# FinalSch.net
KiCad netlist of a schematic drawn in EAGLE
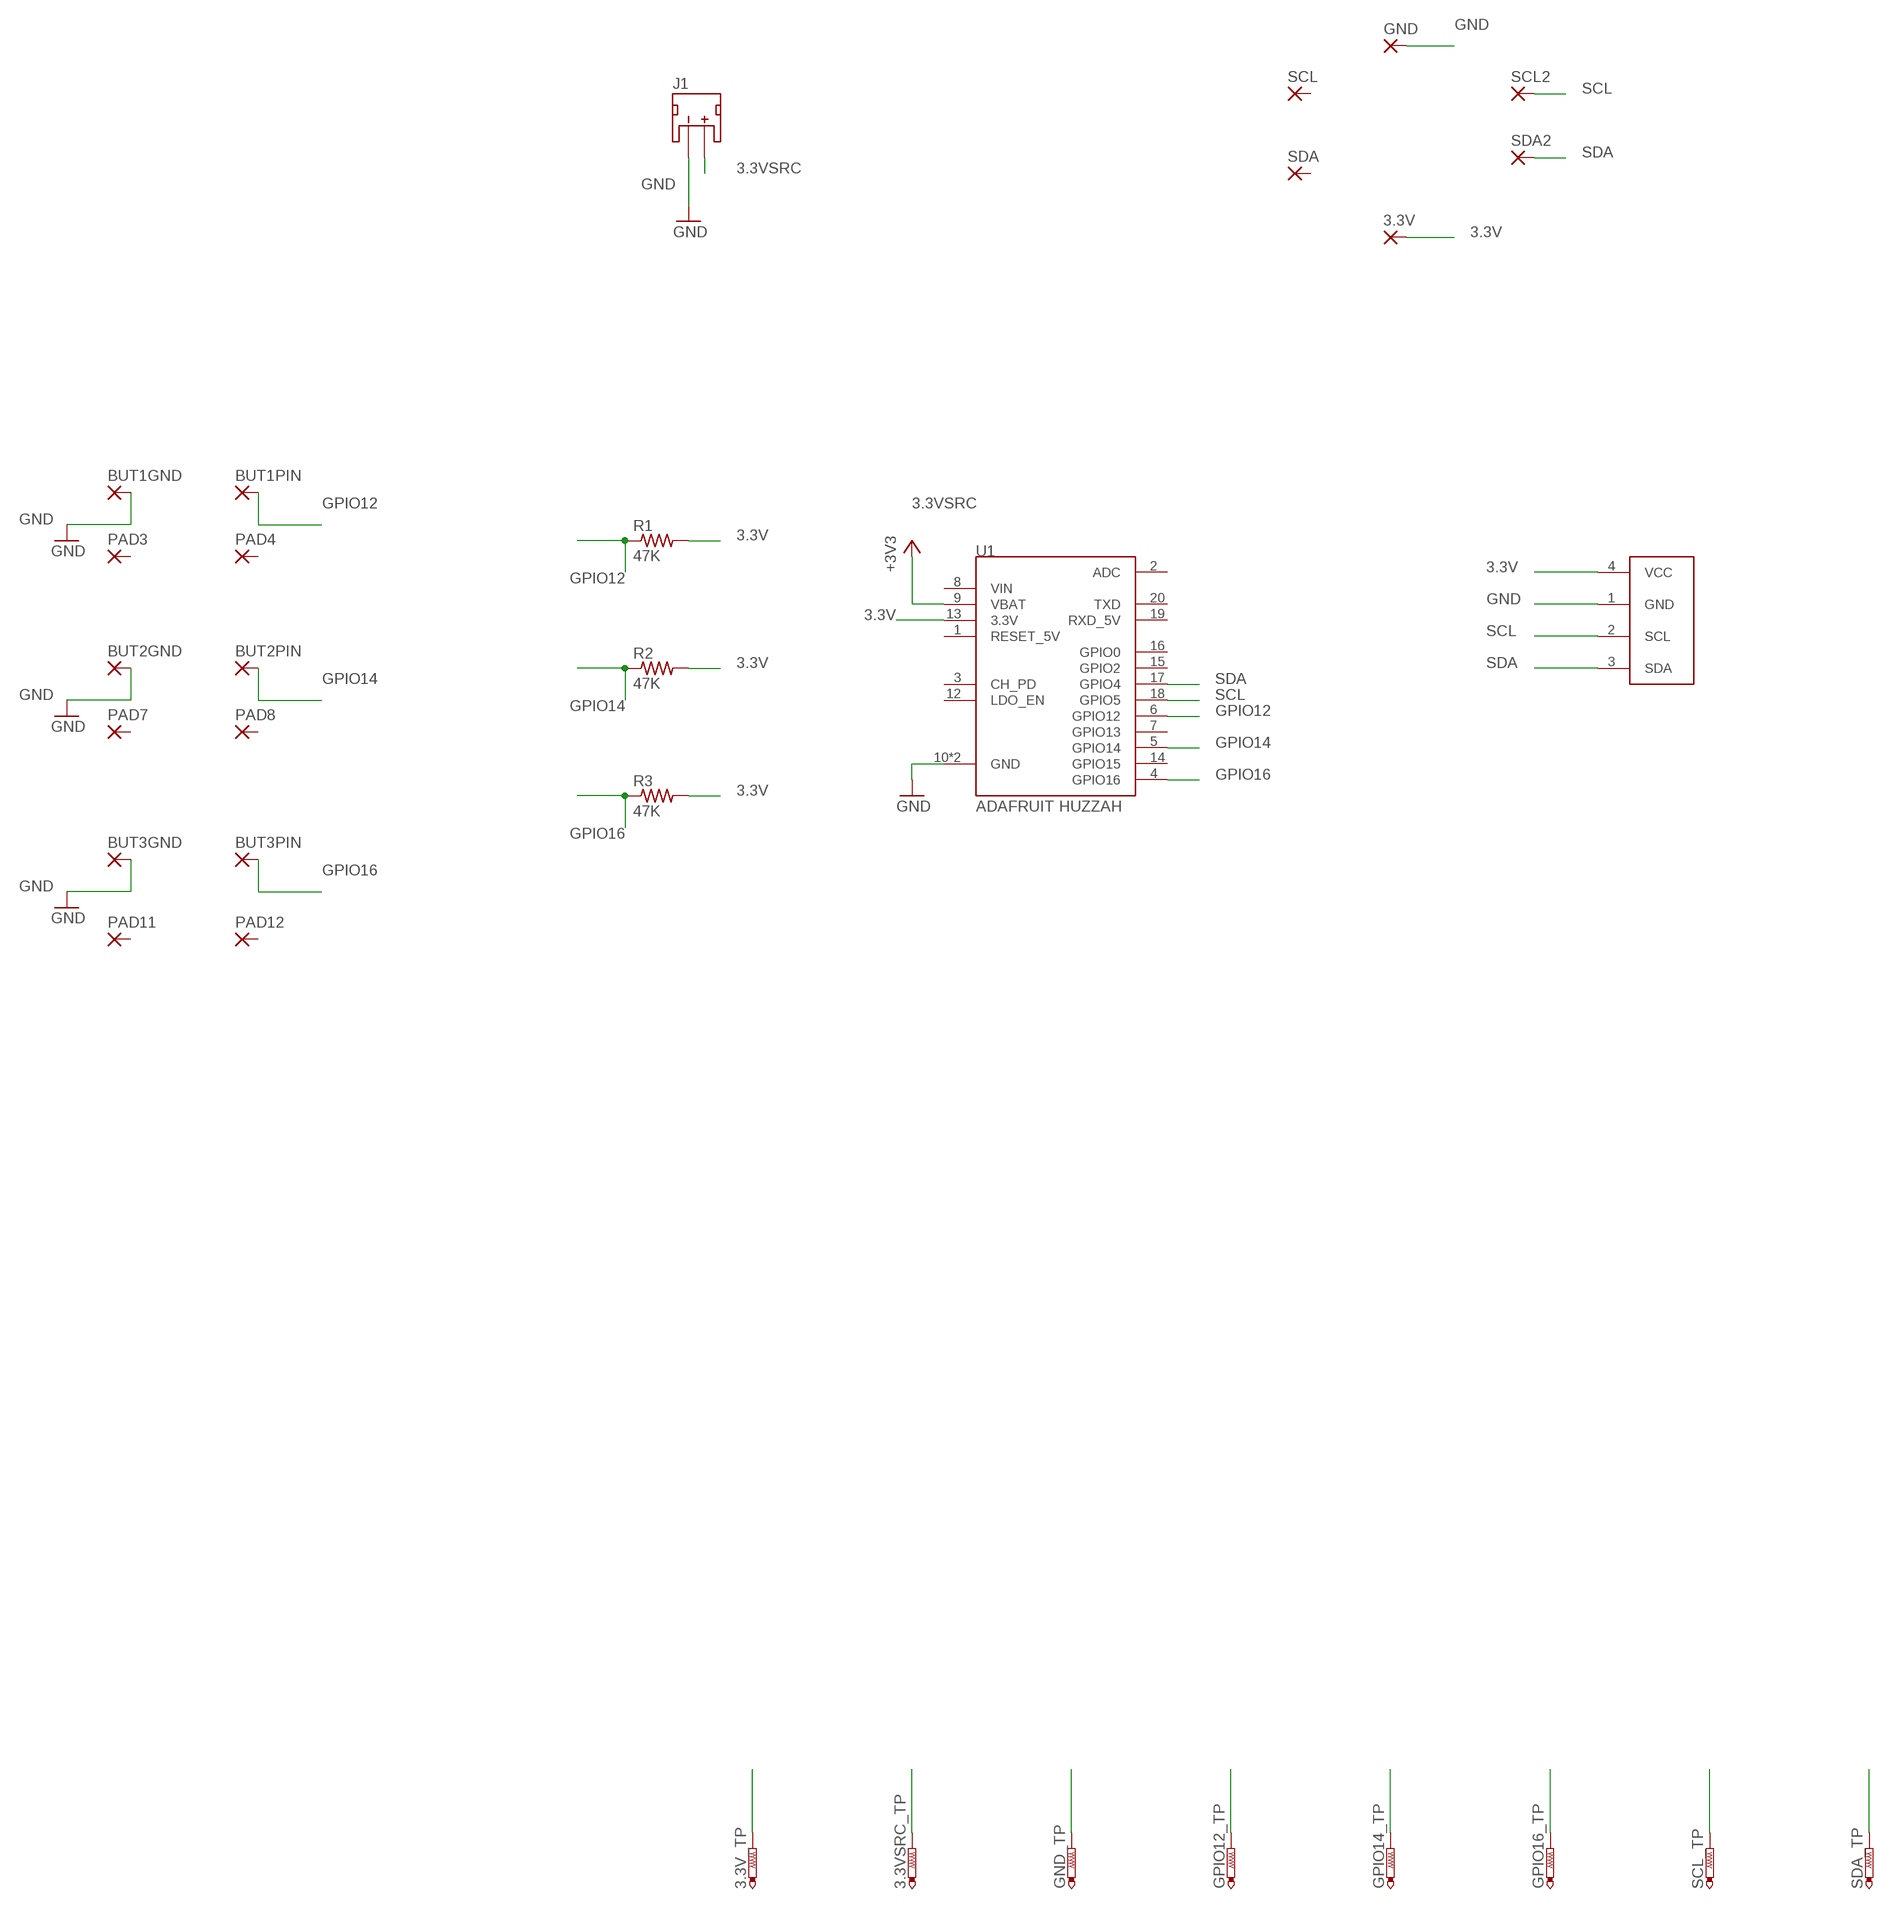
[diagram p0: schematic, sheet 1]

(export (version "E")
  (design (tool "Eeschema 10.0.6"))
  (components
    (comp (ref "3.3V")
      (value "2,54/1,1")
      (footprint "eagle-import:2,54_1,1")
      (libsource (lib "eagle-import") (part "2,54/1,1"))
    )
    (comp (ref "3.3VSRC_TP")
      (value "PTR1B1,27")
      (footprint "eagle-import:B1,27")
      (libsource (lib "eagle-import") (part "PTR1B1,27"))
    )
    (comp (ref "3.3V_TP")
      (value "PTR1B1,27")
      (footprint "eagle-import:B1,27")
      (libsource (lib "eagle-import") (part "PTR1B1,27"))
    )
    (comp (ref "BUT1GND")
      (value "SMD2")
      (footprint "eagle-import:SMD1,27-2,54")
      (libsource (lib "eagle-import") (part "SMD2"))
    )
    (comp (ref "BUT1PIN")
      (value "SMD2")
      (footprint "eagle-import:SMD1,27-2,54")
      (libsource (lib "eagle-import") (part "SMD2"))
    )
    (comp (ref "BUT2GND")
      (value "SMD2")
      (footprint "eagle-import:SMD1,27-2,54")
      (libsource (lib "eagle-import") (part "SMD2"))
    )
    (comp (ref "BUT2PIN")
      (value "SMD2")
      (footprint "eagle-import:SMD1,27-2,54")
      (libsource (lib "eagle-import") (part "SMD2"))
    )
    (comp (ref "BUT3GND")
      (value "SMD2")
      (footprint "eagle-import:SMD1,27-2,54")
      (libsource (lib "eagle-import") (part "SMD2"))
    )
    (comp (ref "BUT3PIN")
      (value "SMD2")
      (footprint "eagle-import:SMD1,27-2,54")
      (libsource (lib "eagle-import") (part "SMD2"))
    )
    (comp (ref "GND")
      (value "2,54/1,1")
      (footprint "eagle-import:2,54_1,1")
      (libsource (lib "eagle-import") (part "2,54/1,1"))
    )
    (comp (ref "GND_TP")
      (value "PTR1B1,27")
      (footprint "eagle-import:B1,27")
      (libsource (lib "eagle-import") (part "PTR1B1,27"))
    )
    (comp (ref "GPIO12_TP")
      (value "PTR1B1,27")
      (footprint "eagle-import:B1,27")
      (libsource (lib "eagle-import") (part "PTR1B1,27"))
    )
    (comp (ref "GPIO14_TP")
      (value "PTR1B1,27")
      (footprint "eagle-import:B1,27")
      (libsource (lib "eagle-import") (part "PTR1B1,27"))
    )
    (comp (ref "GPIO16_TP")
      (value "PTR1B1,27")
      (footprint "eagle-import:B1,27")
      (libsource (lib "eagle-import") (part "PTR1B1,27"))
    )
    (comp (ref "J1")
      (value "JST_2MM_MALE")
      (footprint "eagle-import:JST-2-SMD")
      (libsource (lib "eagle-import") (part "JST_2MM_MALE"))
    )
    (comp (ref "PAD3")
      (value "SMD2")
      (footprint "eagle-import:SMD1,27-2,54")
      (libsource (lib "eagle-import") (part "SMD2"))
    )
    (comp (ref "PAD4")
      (value "SMD2")
      (footprint "eagle-import:SMD1,27-2,54")
      (libsource (lib "eagle-import") (part "SMD2"))
    )
    (comp (ref "PAD7")
      (value "SMD2")
      (footprint "eagle-import:SMD1,27-2,54")
      (libsource (lib "eagle-import") (part "SMD2"))
    )
    (comp (ref "PAD8")
      (value "SMD2")
      (footprint "eagle-import:SMD1,27-2,54")
      (libsource (lib "eagle-import") (part "SMD2"))
    )
    (comp (ref "PAD11")
      (value "SMD2")
      (footprint "eagle-import:SMD1,27-2,54")
      (libsource (lib "eagle-import") (part "SMD2"))
    )
    (comp (ref "PAD12")
      (value "SMD2")
      (footprint "eagle-import:SMD1,27-2,54")
      (libsource (lib "eagle-import") (part "SMD2"))
    )
    (comp (ref "R1")
      (value "47K")
      (footprint "eagle-import:R0805")
      (libsource (lib "eagle-import") (part "R47K-0805"))
    )
    (comp (ref "R2")
      (value "47K")
      (footprint "eagle-import:R0805")
      (libsource (lib "eagle-import") (part "R47K-0805"))
    )
    (comp (ref "R3")
      (value "47K")
      (footprint "eagle-import:R0805")
      (libsource (lib "eagle-import") (part "R47K-0805"))
    )
    (comp (ref "SCL")
      (value "2,54/1,1")
      (footprint "eagle-import:2,54_1,1")
      (libsource (lib "eagle-import") (part "2,54/1,1"))
    )
    (comp (ref "SCL2")
      (value "2,54/1,1")
      (footprint "eagle-import:2,54_1,1")
      (libsource (lib "eagle-import") (part "2,54/1,1"))
    )
    (comp (ref "SCL_TP")
      (value "PTR1B1,27")
      (footprint "eagle-import:B1,27")
      (libsource (lib "eagle-import") (part "PTR1B1,27"))
    )
    (comp (ref "SDA")
      (value "2,54/1,1")
      (footprint "eagle-import:2,54_1,1")
      (libsource (lib "eagle-import") (part "2,54/1,1"))
    )
    (comp (ref "SDA2")
      (value "2,54/1,1")
      (footprint "eagle-import:2,54_1,1")
      (libsource (lib "eagle-import") (part "2,54/1,1"))
    )
    (comp (ref "SDA_TP")
      (value "PTR1B1,27")
      (footprint "eagle-import:B1,27")
      (libsource (lib "eagle-import") (part "PTR1B1,27"))
    )
    (comp (ref "U$1")
      (value "I2C_OLED")
      (footprint "eagle-import:I2C_OLED_PACKAGE")
      (libsource (lib "eagle-import") (part "I2C_OLED"))
    )
    (comp (ref "U1")
      (value "ADAFRUIT_HEZZAH")
      (footprint "eagle-import:ADAFRUIT_HUZZAH")
      (libsource (lib "eagle-import") (part "ADAFRUIT_HEZZAH"))
    )
  )
  (nets
    (net (code "1") (name "+3V3") (class "Default")
      (node (ref "3.3VSRC_TP") (pin "TP") (pinfunction "TP_TP") (pintype "input"))
      (node (ref "J1") (pin "2") (pinfunction "+_2") (pintype "bidirectional"))
      (node (ref "U1") (pin "9") (pinfunction "VBAT_9") (pintype "bidirectional"))
    )
    (net (code "2") (name "/3.3V") (class "Default")
      (node (ref "3.3V") (pin "1") (pinfunction "P_1") (pintype "passive"))
      (node (ref "3.3V_TP") (pin "TP") (pinfunction "TP_TP") (pintype "input"))
      (node (ref "R1") (pin "2") (pinfunction "2_2") (pintype "passive"))
      (node (ref "R2") (pin "2") (pinfunction "2_2") (pintype "passive"))
      (node (ref "R3") (pin "2") (pinfunction "2_2") (pintype "passive"))
      (node (ref "U$1") (pin "4") (pinfunction "VCC_4") (pintype "bidirectional"))
      (node (ref "U1") (pin "13") (pinfunction "3.3V_13") (pintype "bidirectional"))
    )
    (net (code "3") (name "/GPIO12") (class "Default")
      (node (ref "BUT1PIN") (pin "1") (pinfunction "P_1") (pintype "passive"))
      (node (ref "GPIO12_TP") (pin "TP") (pinfunction "TP_TP") (pintype "input"))
      (node (ref "R1") (pin "1") (pinfunction "1_1") (pintype "passive"))
      (node (ref "U1") (pin "6") (pinfunction "GPIO12_6") (pintype "bidirectional"))
    )
    (net (code "4") (name "/GPIO14") (class "Default")
      (node (ref "BUT2PIN") (pin "1") (pinfunction "P_1") (pintype "passive"))
      (node (ref "GPIO14_TP") (pin "TP") (pinfunction "TP_TP") (pintype "input"))
      (node (ref "R2") (pin "1") (pinfunction "1_1") (pintype "passive"))
      (node (ref "U1") (pin "5") (pinfunction "GPIO14_5") (pintype "bidirectional"))
    )
    (net (code "5") (name "/GPIO16") (class "Default")
      (node (ref "BUT3PIN") (pin "1") (pinfunction "P_1") (pintype "passive"))
      (node (ref "GPIO16_TP") (pin "TP") (pinfunction "TP_TP") (pintype "input"))
      (node (ref "R3") (pin "1") (pinfunction "1_1") (pintype "passive"))
      (node (ref "U1") (pin "4") (pinfunction "GPIO16_4") (pintype "bidirectional"))
    )
    (net (code "6") (name "/SCL") (class "Default")
      (node (ref "SCL2") (pin "1") (pinfunction "P_1") (pintype "passive"))
      (node (ref "SCL_TP") (pin "TP") (pinfunction "TP_TP") (pintype "input"))
      (node (ref "U$1") (pin "2") (pinfunction "SCL_2") (pintype "bidirectional"))
      (node (ref "U1") (pin "18") (pinfunction "GPIO5_18") (pintype "bidirectional"))
    )
    (net (code "7") (name "/SDA") (class "Default")
      (node (ref "SDA2") (pin "1") (pinfunction "P_1") (pintype "passive"))
      (node (ref "SDA_TP") (pin "TP") (pinfunction "TP_TP") (pintype "input"))
      (node (ref "U$1") (pin "3") (pinfunction "SDA_3") (pintype "bidirectional"))
      (node (ref "U1") (pin "17") (pinfunction "GPIO4_17") (pintype "bidirectional"))
    )
    (net (code "8") (name "GND") (class "Default")
      (node (ref "BUT1GND") (pin "1") (pinfunction "P_1") (pintype "passive"))
      (node (ref "BUT2GND") (pin "1") (pinfunction "P_1") (pintype "passive"))
      (node (ref "BUT3GND") (pin "1") (pinfunction "P_1") (pintype "passive"))
      (node (ref "GND") (pin "1") (pinfunction "P_1") (pintype "passive"))
      (node (ref "GND_TP") (pin "TP") (pinfunction "TP_TP") (pintype "input"))
      (node (ref "J1") (pin "1") (pinfunction "-_1") (pintype "bidirectional"))
      (node (ref "U$1") (pin "1") (pinfunction "GND_1") (pintype "bidirectional"))
      (node (ref "U1") (pin "10") (pinfunction "GND_10") (pintype "bidirectional"))
      (node (ref "U1") (pin "11") (pinfunction "GND_11") (pintype "bidirectional"))
    )
    (net (code "9") (name "unconnected-(J1-PAD1-PadNC1)") (class "Default")
      (node (ref "J1") (pin "NC1") (pinfunction "PAD1_NC1") (pintype "bidirectional"))
    )
    (net (code "10") (name "unconnected-(J1-PAD2-PadNC2)") (class "Default")
      (node (ref "J1") (pin "NC2") (pinfunction "PAD2_NC2") (pintype "bidirectional"))
    )
    (net (code "11") (name "unconnected-(PAD3-P-Pad1)") (class "Default")
      (node (ref "PAD3") (pin "1") (pinfunction "P_1") (pintype "passive"))
    )
    (net (code "12") (name "unconnected-(PAD4-P-Pad1)") (class "Default")
      (node (ref "PAD4") (pin "1") (pinfunction "P_1") (pintype "passive"))
    )
    (net (code "13") (name "unconnected-(PAD7-P-Pad1)") (class "Default")
      (node (ref "PAD7") (pin "1") (pinfunction "P_1") (pintype "passive"))
    )
    (net (code "14") (name "unconnected-(PAD8-P-Pad1)") (class "Default")
      (node (ref "PAD8") (pin "1") (pinfunction "P_1") (pintype "passive"))
    )
    (net (code "15") (name "unconnected-(PAD11-P-Pad1)") (class "Default")
      (node (ref "PAD11") (pin "1") (pinfunction "P_1") (pintype "passive"))
    )
    (net (code "16") (name "unconnected-(PAD12-P-Pad1)") (class "Default")
      (node (ref "PAD12") (pin "1") (pinfunction "P_1") (pintype "passive"))
    )
    (net (code "17") (name "unconnected-(SCL-P-Pad1)") (class "Default")
      (node (ref "SCL") (pin "1") (pinfunction "P_1") (pintype "passive"))
    )
    (net (code "18") (name "unconnected-(SDA-P-Pad1)") (class "Default")
      (node (ref "SDA") (pin "1") (pinfunction "P_1") (pintype "passive"))
    )
    (net (code "19") (name "unconnected-(U1-ADC-Pad2)") (class "Default")
      (node (ref "U1") (pin "2") (pinfunction "ADC_2") (pintype "bidirectional"))
    )
    (net (code "20") (name "unconnected-(U1-CH_PD-Pad3)") (class "Default")
      (node (ref "U1") (pin "3") (pinfunction "CH_PD_3") (pintype "bidirectional"))
    )
    (net (code "21") (name "unconnected-(U1-GPIO0-Pad16)") (class "Default")
      (node (ref "U1") (pin "16") (pinfunction "GPIO0_16") (pintype "bidirectional"))
    )
    (net (code "22") (name "unconnected-(U1-GPIO2-Pad15)") (class "Default")
      (node (ref "U1") (pin "15") (pinfunction "GPIO2_15") (pintype "bidirectional"))
    )
    (net (code "23") (name "unconnected-(U1-GPIO13-Pad7)") (class "Default")
      (node (ref "U1") (pin "7") (pinfunction "GPIO13_7") (pintype "bidirectional"))
    )
    (net (code "24") (name "unconnected-(U1-GPIO15-Pad14)") (class "Default")
      (node (ref "U1") (pin "14") (pinfunction "GPIO15_14") (pintype "bidirectional"))
    )
    (net (code "25") (name "unconnected-(U1-LDO_EN-Pad12)") (class "Default")
      (node (ref "U1") (pin "12") (pinfunction "LDO_EN_12") (pintype "bidirectional"))
    )
    (net (code "26") (name "unconnected-(U1-RESET_5V-Pad1)") (class "Default")
      (node (ref "U1") (pin "1") (pinfunction "RESET_5V_1") (pintype "bidirectional"))
    )
    (net (code "27") (name "unconnected-(U1-RXD_5V-Pad19)") (class "Default")
      (node (ref "U1") (pin "19") (pinfunction "RXD_5V_19") (pintype "bidirectional"))
    )
    (net (code "28") (name "unconnected-(U1-TXD-Pad20)") (class "Default")
      (node (ref "U1") (pin "20") (pinfunction "TXD_20") (pintype "bidirectional"))
    )
    (net (code "29") (name "unconnected-(U1-VIN-Pad8)") (class "Default")
      (node (ref "U1") (pin "8") (pinfunction "VIN_8") (pintype "bidirectional"))
    )
  )
)
